# msp430.net
KiCad netlist of a schematic drawn in EAGLE
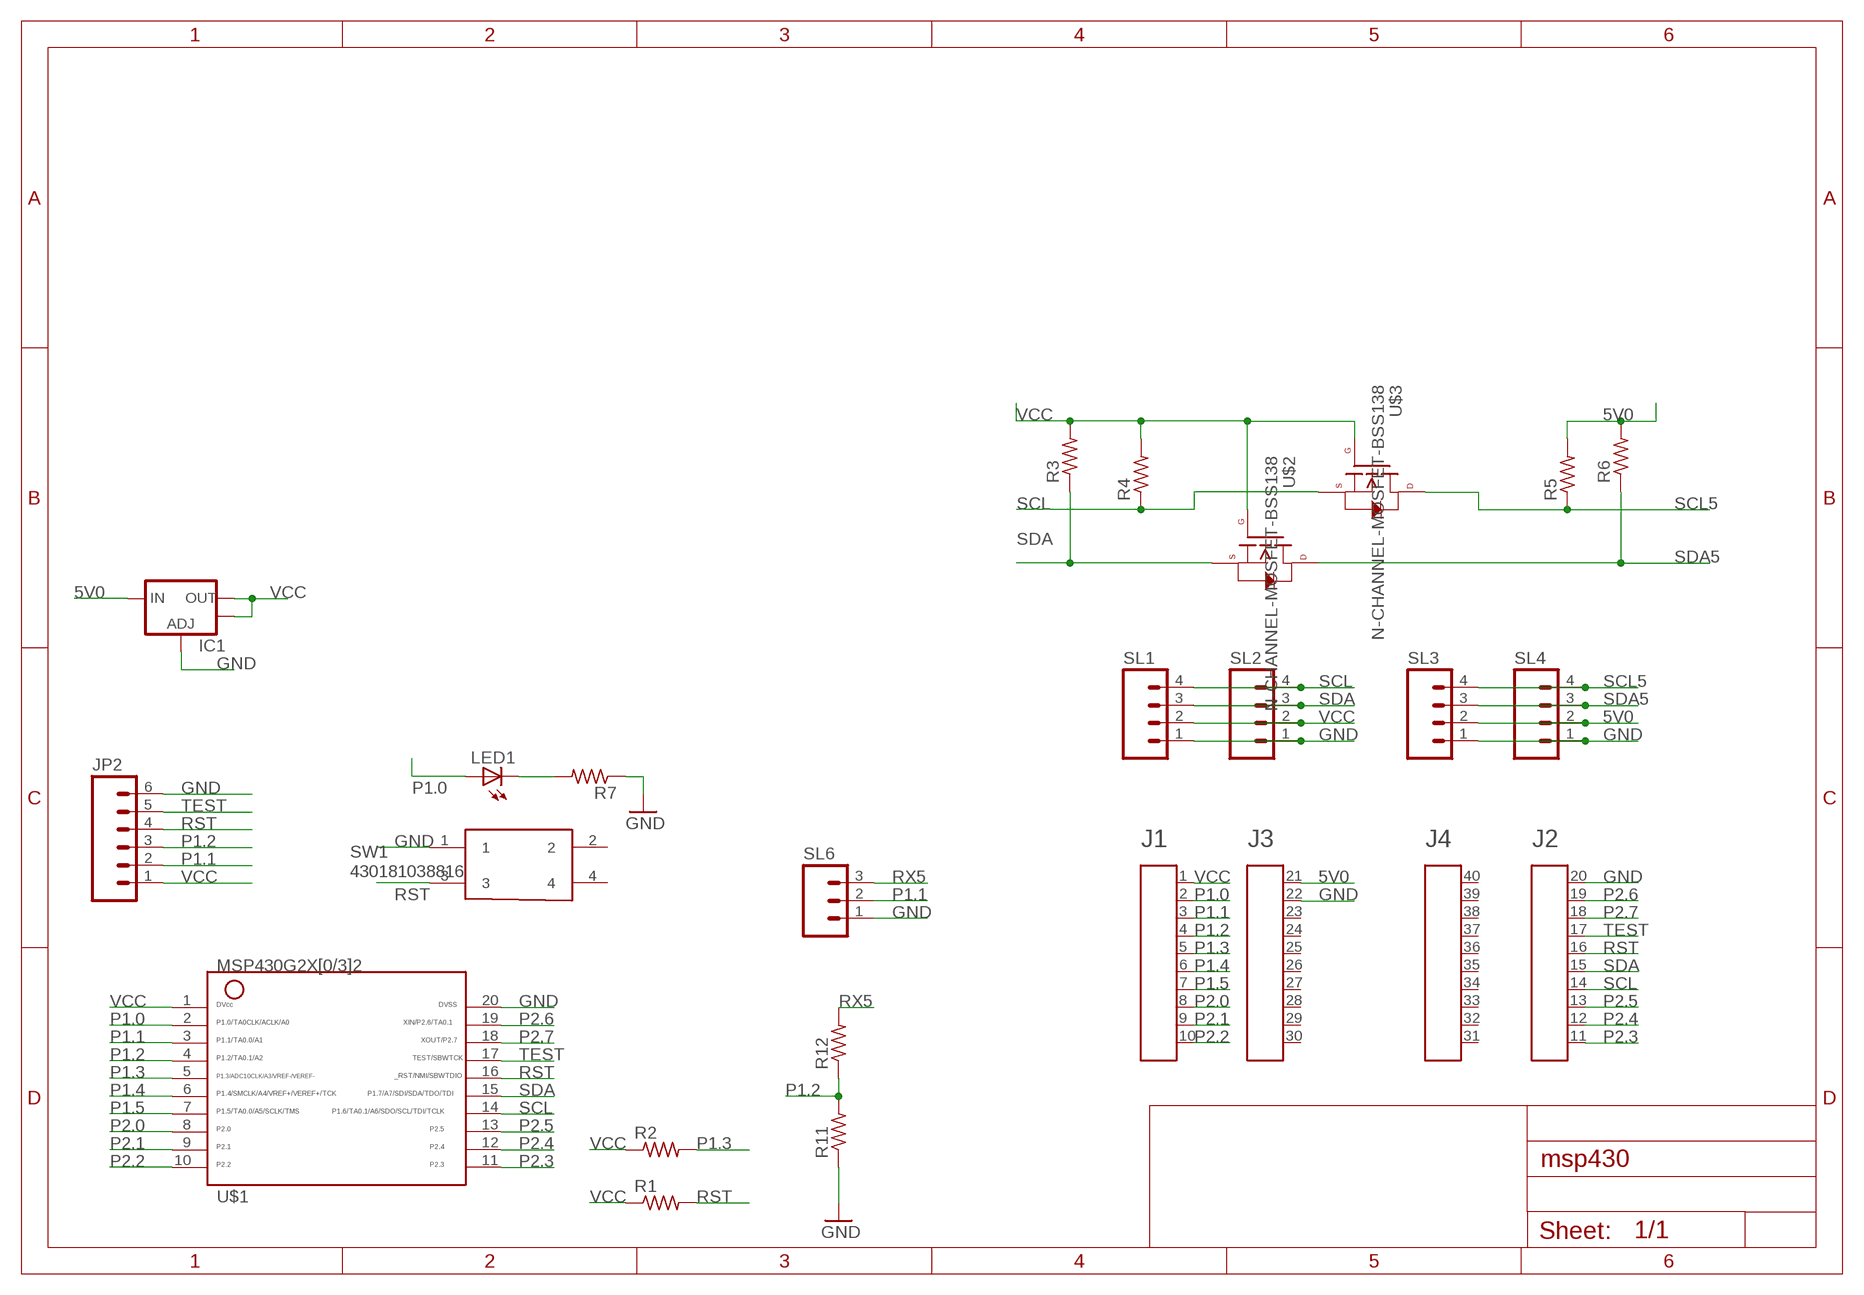
[diagram p0: schematic, sheet 1]

(export (version "E")
  (design (tool "Eeschema 10.0.6"))
  (components
    (comp (ref "A1")
      (value "HEADER4X10-BOOSTERPACK")
      (footprint "eagle-import:4X10-BOOSTERPACK")
      (libsource (lib "eagle-import") (part "HEADER4X10-BOOSTERPACK"))
    )
    (comp (ref "IC1")
      (value "V_REG_LM1117SOT223")
      (footprint "eagle-import:SOT223")
      (libsource (lib "eagle-import") (part "V_REG_LM1117SOT223"))
    )
    (comp (ref "JP2")
      (value "M06LOCK")
      (footprint "eagle-import:1X06_LOCK")
      (libsource (lib "eagle-import") (part "M06LOCK"))
    )
    (comp (ref "LED1")
      (value "LEDCHIPLED_0805")
      (footprint "eagle-import:CHIPLED_0805")
      (libsource (lib "eagle-import") (part "LEDCHIPLED_0805"))
    )
    (comp (ref "R1")
      (value "R-US_M0805")
      (footprint "eagle-import:M0805")
      (libsource (lib "eagle-import") (part "R-US_M0805"))
    )
    (comp (ref "R2")
      (value "R-US_M0805")
      (footprint "eagle-import:M0805")
      (libsource (lib "eagle-import") (part "R-US_M0805"))
    )
    (comp (ref "R3")
      (value "R-US_M0805")
      (footprint "eagle-import:M0805")
      (libsource (lib "eagle-import") (part "R-US_M0805"))
    )
    (comp (ref "R4")
      (value "R-US_M0805")
      (footprint "eagle-import:M0805")
      (libsource (lib "eagle-import") (part "R-US_M0805"))
    )
    (comp (ref "R5")
      (value "R-US_M0805")
      (footprint "eagle-import:M0805")
      (libsource (lib "eagle-import") (part "R-US_M0805"))
    )
    (comp (ref "R6")
      (value "R-US_M0805")
      (footprint "eagle-import:M0805")
      (libsource (lib "eagle-import") (part "R-US_M0805"))
    )
    (comp (ref "R7")
      (value "R-US_M0805")
      (footprint "eagle-import:M0805")
      (libsource (lib "eagle-import") (part "R-US_M0805"))
    )
    (comp (ref "R11")
      (value "R-US_M0805")
      (footprint "eagle-import:M0805")
      (libsource (lib "eagle-import") (part "R-US_M0805"))
    )
    (comp (ref "R12")
      (value "R-US_M0805")
      (footprint "eagle-import:M0805")
      (libsource (lib "eagle-import") (part "R-US_M0805"))
    )
    (comp (ref "SL1")
      (value "M04")
      (footprint "eagle-import:04P")
      (libsource (lib "eagle-import") (part "M04"))
    )
    (comp (ref "SL2")
      (value "M04")
      (footprint "eagle-import:04P")
      (libsource (lib "eagle-import") (part "M04"))
    )
    (comp (ref "SL3")
      (value "M04")
      (footprint "eagle-import:04P")
      (libsource (lib "eagle-import") (part "M04"))
    )
    (comp (ref "SL4")
      (value "M04")
      (footprint "eagle-import:04P")
      (libsource (lib "eagle-import") (part "M04"))
    )
    (comp (ref "SL6")
      (value "M03")
      (footprint "eagle-import:03P")
      (libsource (lib "eagle-import") (part "M03"))
    )
    (comp (ref "SW1")
      (value "430181038816")
      (footprint "eagle-import:430181038816")
      (libsource (lib "eagle-import") (part "430181038816"))
    )
    (comp (ref "U$1")
      (value "G2X[0/3]2---N20")
      (footprint "eagle-import:N20")
      (libsource (lib "eagle-import") (part "G2X[0/3]2---N20"))
    )
    (comp (ref "U$2")
      (value "N-CHANNEL-MOSFET-BSS138")
      (footprint "eagle-import:SOT23-3")
      (libsource (lib "eagle-import") (part "N-CHANNEL-MOSFET-BSS138"))
    )
    (comp (ref "U$3")
      (value "N-CHANNEL-MOSFET-BSS138")
      (footprint "eagle-import:SOT23-3")
      (libsource (lib "eagle-import") (part "N-CHANNEL-MOSFET-BSS138"))
    )
  )
  (nets
    (net (code "1") (name "/5V0") (class "Default")
      (node (ref "A1") (pin "21") (pinfunction "P$21_21") (pintype "bidirectional"))
      (node (ref "IC1") (pin "3") (pinfunction "IN_3") (pintype "input"))
      (node (ref "R5") (pin "2") (pinfunction "2_2") (pintype "passive"))
      (node (ref "R6") (pin "2") (pinfunction "2_2") (pintype "passive"))
      (node (ref "SL3") (pin "2") (pinfunction "2_2") (pintype "passive"))
      (node (ref "SL4") (pin "2") (pinfunction "2_2") (pintype "passive"))
    )
    (net (code "2") (name "/P1.0") (class "Default")
      (node (ref "A1") (pin "2") (pinfunction "P$2_2") (pintype "bidirectional"))
      (node (ref "LED1") (pin "A") (pinfunction "A_A") (pintype "passive"))
      (node (ref "U$1") (pin "2") (pinfunction "2_2") (pintype "bidirectional"))
    )
    (net (code "3") (name "/P1.1") (class "Default")
      (node (ref "A1") (pin "3") (pinfunction "P$3_3") (pintype "bidirectional"))
      (node (ref "JP2") (pin "2") (pinfunction "2_2") (pintype "passive"))
      (node (ref "SL6") (pin "2") (pinfunction "2_2") (pintype "passive"))
      (node (ref "U$1") (pin "3") (pinfunction "3_3") (pintype "bidirectional"))
    )
    (net (code "4") (name "/P1.2") (class "Default")
      (node (ref "A1") (pin "4") (pinfunction "P$4_4") (pintype "bidirectional"))
      (node (ref "JP2") (pin "3") (pinfunction "3_3") (pintype "passive"))
      (node (ref "R11") (pin "2") (pinfunction "2_2") (pintype "passive"))
      (node (ref "R12") (pin "1") (pinfunction "1_1") (pintype "passive"))
      (node (ref "U$1") (pin "4") (pinfunction "4_4") (pintype "bidirectional"))
    )
    (net (code "5") (name "/P1.3") (class "Default")
      (node (ref "A1") (pin "5") (pinfunction "P$5_5") (pintype "bidirectional"))
      (node (ref "R2") (pin "2") (pinfunction "2_2") (pintype "passive"))
      (node (ref "U$1") (pin "5") (pinfunction "5_5") (pintype "bidirectional"))
    )
    (net (code "6") (name "/P1.4") (class "Default")
      (node (ref "A1") (pin "6") (pinfunction "P$6_6") (pintype "bidirectional"))
      (node (ref "U$1") (pin "6") (pinfunction "6_6") (pintype "bidirectional"))
    )
    (net (code "7") (name "/P1.5") (class "Default")
      (node (ref "A1") (pin "7") (pinfunction "P$7_7") (pintype "bidirectional"))
      (node (ref "U$1") (pin "7") (pinfunction "7_7") (pintype "bidirectional"))
    )
    (net (code "8") (name "/P2.0") (class "Default")
      (node (ref "A1") (pin "8") (pinfunction "P$8_8") (pintype "bidirectional"))
      (node (ref "U$1") (pin "8") (pinfunction "8_8") (pintype "bidirectional"))
    )
    (net (code "9") (name "/P2.1") (class "Default")
      (node (ref "A1") (pin "9") (pinfunction "P$9_9") (pintype "bidirectional"))
      (node (ref "U$1") (pin "9") (pinfunction "9_9") (pintype "bidirectional"))
    )
    (net (code "10") (name "/P2.2") (class "Default")
      (node (ref "A1") (pin "10") (pinfunction "P$10_10") (pintype "bidirectional"))
      (node (ref "U$1") (pin "10") (pinfunction "10_10") (pintype "bidirectional"))
    )
    (net (code "11") (name "/P2.3") (class "Default")
      (node (ref "A1") (pin "11") (pinfunction "P$11_11") (pintype "bidirectional"))
      (node (ref "U$1") (pin "11") (pinfunction "11_11") (pintype "bidirectional"))
    )
    (net (code "12") (name "/P2.4") (class "Default")
      (node (ref "A1") (pin "12") (pinfunction "P$12_12") (pintype "bidirectional"))
      (node (ref "U$1") (pin "12") (pinfunction "12_12") (pintype "bidirectional"))
    )
    (net (code "13") (name "/P2.5") (class "Default")
      (node (ref "A1") (pin "13") (pinfunction "P$13_13") (pintype "bidirectional"))
      (node (ref "U$1") (pin "13") (pinfunction "13_13") (pintype "bidirectional"))
    )
    (net (code "14") (name "/P2.6") (class "Default")
      (node (ref "A1") (pin "19") (pinfunction "P$19_19") (pintype "bidirectional"))
      (node (ref "U$1") (pin "19") (pinfunction "19_19") (pintype "bidirectional"))
    )
    (net (code "15") (name "/P2.7") (class "Default")
      (node (ref "A1") (pin "18") (pinfunction "P$18_18") (pintype "bidirectional"))
      (node (ref "U$1") (pin "18") (pinfunction "18_18") (pintype "bidirectional"))
    )
    (net (code "16") (name "/RST") (class "Default")
      (node (ref "A1") (pin "16") (pinfunction "P$16_16") (pintype "bidirectional"))
      (node (ref "JP2") (pin "4") (pinfunction "4_4") (pintype "passive"))
      (node (ref "R1") (pin "2") (pinfunction "2_2") (pintype "passive"))
      (node (ref "SW1") (pin "3") (pinfunction "3_3") (pintype "bidirectional"))
      (node (ref "U$1") (pin "16") (pinfunction "16_16") (pintype "bidirectional"))
    )
    (net (code "17") (name "/RX5") (class "Default")
      (node (ref "R12") (pin "2") (pinfunction "2_2") (pintype "passive"))
      (node (ref "SL6") (pin "3") (pinfunction "3_3") (pintype "passive"))
    )
    (net (code "18") (name "/SCL") (class "Default")
      (node (ref "A1") (pin "14") (pinfunction "P$14_14") (pintype "bidirectional"))
      (node (ref "R4") (pin "1") (pinfunction "1_1") (pintype "passive"))
      (node (ref "SL1") (pin "4") (pinfunction "4_4") (pintype "passive"))
      (node (ref "SL2") (pin "4") (pinfunction "4_4") (pintype "passive"))
      (node (ref "U$1") (pin "14") (pinfunction "14_14") (pintype "bidirectional"))
      (node (ref "U$3") (pin "2") (pinfunction "S_2") (pintype "passive"))
    )
    (net (code "19") (name "/SCL5") (class "Default")
      (node (ref "R5") (pin "1") (pinfunction "1_1") (pintype "passive"))
      (node (ref "SL3") (pin "4") (pinfunction "4_4") (pintype "passive"))
      (node (ref "SL4") (pin "4") (pinfunction "4_4") (pintype "passive"))
      (node (ref "U$3") (pin "3") (pinfunction "D_3") (pintype "passive"))
    )
    (net (code "20") (name "/SDA") (class "Default")
      (node (ref "A1") (pin "15") (pinfunction "P$15_15") (pintype "bidirectional"))
      (node (ref "R3") (pin "1") (pinfunction "1_1") (pintype "passive"))
      (node (ref "SL1") (pin "3") (pinfunction "3_3") (pintype "passive"))
      (node (ref "SL2") (pin "3") (pinfunction "3_3") (pintype "passive"))
      (node (ref "U$1") (pin "15") (pinfunction "15_15") (pintype "bidirectional"))
      (node (ref "U$2") (pin "2") (pinfunction "S_2") (pintype "passive"))
    )
    (net (code "21") (name "/SDA5") (class "Default")
      (node (ref "R6") (pin "1") (pinfunction "1_1") (pintype "passive"))
      (node (ref "SL3") (pin "3") (pinfunction "3_3") (pintype "passive"))
      (node (ref "SL4") (pin "3") (pinfunction "3_3") (pintype "passive"))
      (node (ref "U$2") (pin "3") (pinfunction "D_3") (pintype "passive"))
    )
    (net (code "22") (name "/TEST") (class "Default")
      (node (ref "A1") (pin "17") (pinfunction "P$17_17") (pintype "bidirectional"))
      (node (ref "JP2") (pin "5") (pinfunction "5_5") (pintype "passive"))
      (node (ref "U$1") (pin "17") (pinfunction "17_17") (pintype "bidirectional"))
    )
    (net (code "23") (name "/VCC") (class "Default")
      (node (ref "A1") (pin "1") (pinfunction "P$1_1") (pintype "bidirectional"))
      (node (ref "IC1") (pin "2") (pinfunction "OUT_2") (pintype "output"))
      (node (ref "IC1") (pin "4") (pinfunction "OUT_4") (pintype "output"))
      (node (ref "JP2") (pin "1") (pinfunction "1_1") (pintype "passive"))
      (node (ref "R1") (pin "1") (pinfunction "1_1") (pintype "passive"))
      (node (ref "R2") (pin "1") (pinfunction "1_1") (pintype "passive"))
      (node (ref "R3") (pin "2") (pinfunction "2_2") (pintype "passive"))
      (node (ref "R4") (pin "2") (pinfunction "2_2") (pintype "passive"))
      (node (ref "SL1") (pin "2") (pinfunction "2_2") (pintype "passive"))
      (node (ref "SL2") (pin "2") (pinfunction "2_2") (pintype "passive"))
      (node (ref "U$1") (pin "1") (pinfunction "1_1") (pintype "bidirectional"))
      (node (ref "U$2") (pin "1") (pinfunction "G_1") (pintype "passive"))
      (node (ref "U$3") (pin "1") (pinfunction "G_1") (pintype "passive"))
    )
    (net (code "24") (name "GND") (class "Default")
      (node (ref "A1") (pin "20") (pinfunction "P$20_20") (pintype "bidirectional"))
      (node (ref "A1") (pin "22") (pinfunction "P$22_22") (pintype "bidirectional"))
      (node (ref "IC1") (pin "1") (pinfunction "ADJ_1") (pintype "input"))
      (node (ref "JP2") (pin "6") (pinfunction "6_6") (pintype "passive"))
      (node (ref "R11") (pin "1") (pinfunction "1_1") (pintype "passive"))
      (node (ref "R7") (pin "1") (pinfunction "1_1") (pintype "passive"))
      (node (ref "SL1") (pin "1") (pinfunction "1_1") (pintype "passive"))
      (node (ref "SL2") (pin "1") (pinfunction "1_1") (pintype "passive"))
      (node (ref "SL3") (pin "1") (pinfunction "1_1") (pintype "passive"))
      (node (ref "SL4") (pin "1") (pinfunction "1_1") (pintype "passive"))
      (node (ref "SL6") (pin "1") (pinfunction "1_1") (pintype "passive"))
      (node (ref "SW1") (pin "1") (pinfunction "1_1") (pintype "bidirectional"))
      (node (ref "U$1") (pin "20") (pinfunction "20_20") (pintype "bidirectional"))
    )
    (net (code "25") (name "Net-(LED1-PadC)") (class "Default")
      (node (ref "LED1") (pin "C") (pinfunction "C_C") (pintype "passive"))
      (node (ref "R7") (pin "2") (pinfunction "2_2") (pintype "passive"))
    )
    (net (code "26") (name "unconnected-(A1-P$23-Pad23)") (class "Default")
      (node (ref "A1") (pin "23") (pinfunction "P$23_23") (pintype "bidirectional"))
    )
    (net (code "27") (name "unconnected-(A1-P$24-Pad24)") (class "Default")
      (node (ref "A1") (pin "24") (pinfunction "P$24_24") (pintype "bidirectional"))
    )
    (net (code "28") (name "unconnected-(A1-P$25-Pad25)") (class "Default")
      (node (ref "A1") (pin "25") (pinfunction "P$25_25") (pintype "bidirectional"))
    )
    (net (code "29") (name "unconnected-(A1-P$26-Pad26)") (class "Default")
      (node (ref "A1") (pin "26") (pinfunction "P$26_26") (pintype "bidirectional"))
    )
    (net (code "30") (name "unconnected-(A1-P$27-Pad27)") (class "Default")
      (node (ref "A1") (pin "27") (pinfunction "P$27_27") (pintype "bidirectional"))
    )
    (net (code "31") (name "unconnected-(A1-P$28-Pad28)") (class "Default")
      (node (ref "A1") (pin "28") (pinfunction "P$28_28") (pintype "bidirectional"))
    )
    (net (code "32") (name "unconnected-(A1-P$29-Pad29)") (class "Default")
      (node (ref "A1") (pin "29") (pinfunction "P$29_29") (pintype "bidirectional"))
    )
    (net (code "33") (name "unconnected-(A1-P$30-Pad30)") (class "Default")
      (node (ref "A1") (pin "30") (pinfunction "P$30_30") (pintype "bidirectional"))
    )
    (net (code "34") (name "unconnected-(A1-P$31-Pad31)") (class "Default")
      (node (ref "A1") (pin "31") (pinfunction "P$31_31") (pintype "bidirectional"))
    )
    (net (code "35") (name "unconnected-(A1-P$32-Pad32)") (class "Default")
      (node (ref "A1") (pin "32") (pinfunction "P$32_32") (pintype "bidirectional"))
    )
    (net (code "36") (name "unconnected-(A1-P$33-Pad33)") (class "Default")
      (node (ref "A1") (pin "33") (pinfunction "P$33_33") (pintype "bidirectional"))
    )
    (net (code "37") (name "unconnected-(A1-P$34-Pad34)") (class "Default")
      (node (ref "A1") (pin "34") (pinfunction "P$34_34") (pintype "bidirectional"))
    )
    (net (code "38") (name "unconnected-(A1-P$35-Pad35)") (class "Default")
      (node (ref "A1") (pin "35") (pinfunction "P$35_35") (pintype "bidirectional"))
    )
    (net (code "39") (name "unconnected-(A1-P$36-Pad36)") (class "Default")
      (node (ref "A1") (pin "36") (pinfunction "P$36_36") (pintype "bidirectional"))
    )
    (net (code "40") (name "unconnected-(A1-P$37-Pad37)") (class "Default")
      (node (ref "A1") (pin "37") (pinfunction "P$37_37") (pintype "bidirectional"))
    )
    (net (code "41") (name "unconnected-(A1-P$38-Pad38)") (class "Default")
      (node (ref "A1") (pin "38") (pinfunction "P$38_38") (pintype "bidirectional"))
    )
    (net (code "42") (name "unconnected-(A1-P$39-Pad39)") (class "Default")
      (node (ref "A1") (pin "39") (pinfunction "P$39_39") (pintype "bidirectional"))
    )
    (net (code "43") (name "unconnected-(A1-P$40-Pad40)") (class "Default")
      (node (ref "A1") (pin "40") (pinfunction "P$40_40") (pintype "bidirectional"))
    )
    (net (code "44") (name "unconnected-(SW1-Pad2)") (class "Default")
      (node (ref "SW1") (pin "2") (pinfunction "2_2") (pintype "bidirectional"))
    )
    (net (code "45") (name "unconnected-(SW1-Pad4)") (class "Default")
      (node (ref "SW1") (pin "4") (pinfunction "4_4") (pintype "bidirectional"))
    )
  )
)
